# Accelerometer.net
KiCad netlist of a schematic drawn in Altium Designer
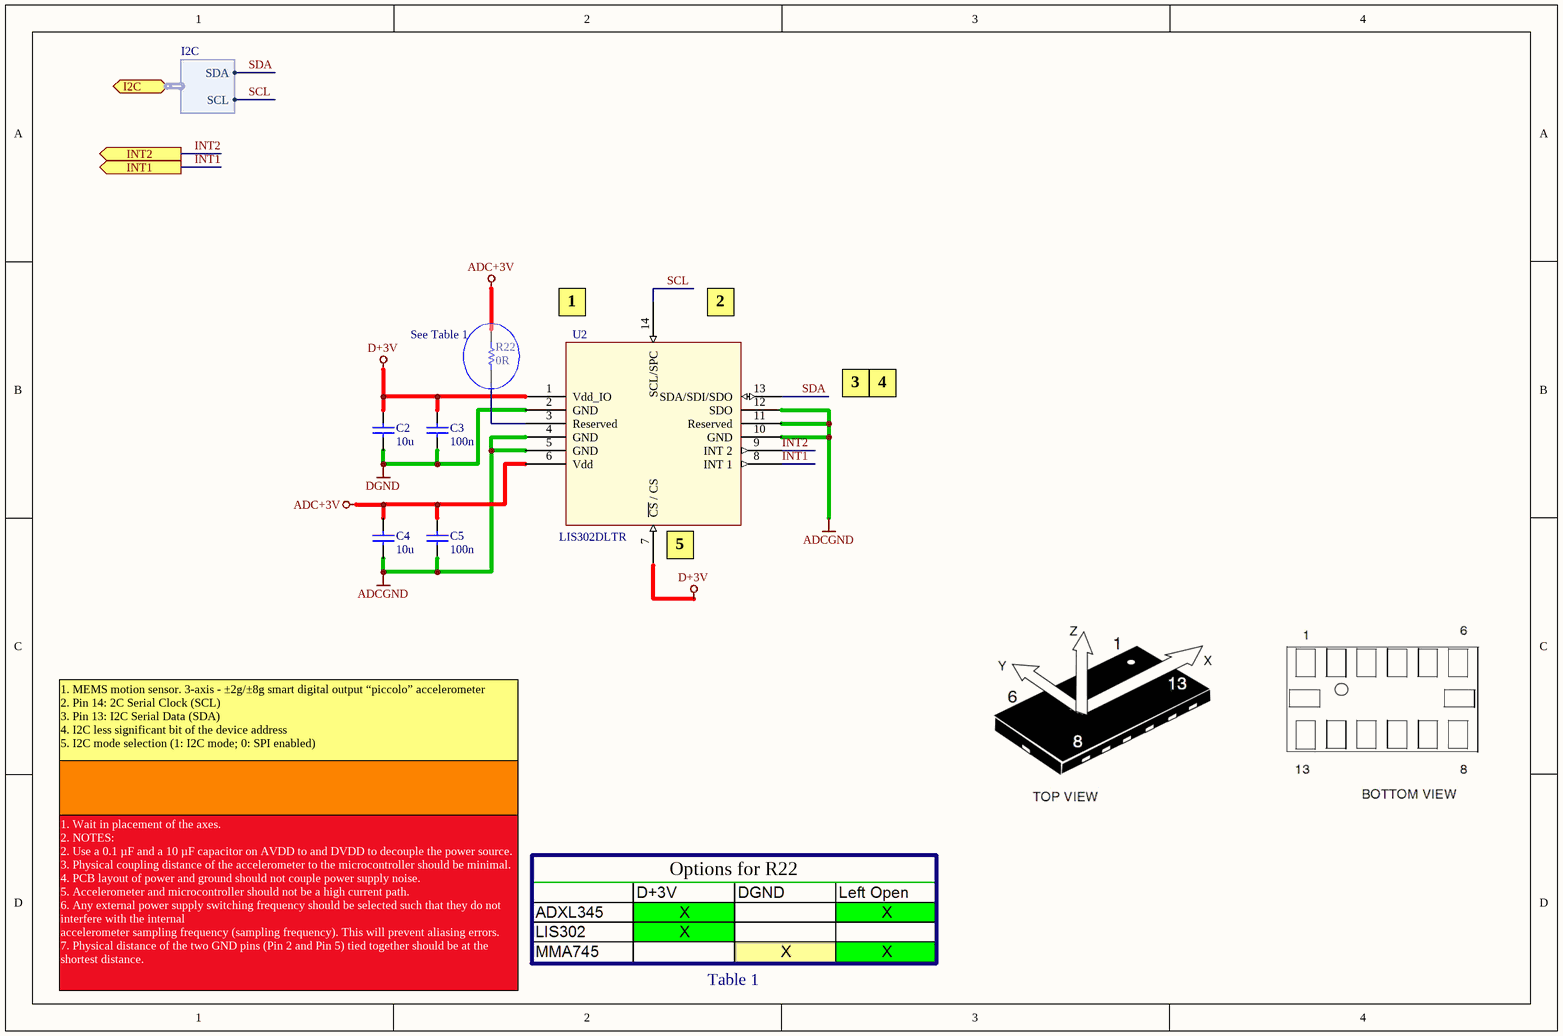
[diagram p0: Accelerometer.SchDoc]

(export (version "E")
  (design (tool "Eeschema 10.0.6"))
  (components
    (comp (ref "C2")
      (value "10u")
      (footprint "CC1608-0603")
      (description "CAP CER 10UF 6.3V X5R 0603")
      (fields (field (name "Comment") "Cap Semi"))
      (libsource (lib "Z1_Project") (part "Cap Semi"))
    )
    (comp (ref "C3")
      (value "100n")
      (footprint "CC-0402-AL")
      (description "Capacitor (Semiconductor SIM Model)")
      (fields (field (name "Comment") "Cap Semi"))
      (libsource (lib "Z1_Project") (part "Cap Semi"))
    )
    (comp (ref "C4")
      (value "10u")
      (footprint "CC1608-0603")
      (description "CAP CER 10UF 6.3V X5R 0603")
      (fields (field (name "Comment") "Cap Semi"))
      (libsource (lib "Z1_Project") (part "Cap Semi"))
    )
    (comp (ref "C5")
      (value "100n")
      (footprint "CC-0402-AL")
      (description "Capacitor (Semiconductor SIM Model)")
      (fields (field (name "Comment") "Cap Semi"))
      (libsource (lib "Z1_Project") (part "Cap Semi"))
    )
    (comp (ref "R22")
      (value "0R")
      (footprint "CR-0402-AL")
      (description "Semiconductor Resistor")
      (fields (field (name "MANUFACTURER") "Generic Components") (field (name "Comment") "Res Semi"))
      (libsource (lib "Z1_Project") (part "Res Semi"))
    )
    (comp (ref "U2")
      (value "LIS302DLTR")
      (footprint "LGA-3x5x1 0.8 - 1.5")
      (description "MEMS motion sensor  3-axis - ±2g/±8g smart digital output “piccolo” accelerometer")
      (libsource (lib "Z1_Project") (part "LIS302DL"))
    )
  )
  (nets
    (net (code "2") (name "/INT1") (class "Default")
      (node (ref "U2") (pin "8") (pinfunction "INT_1_8") (pintype "output"))
    )
    (net (code "3") (name "/INT2") (class "Default")
      (node (ref "U2") (pin "9") (pinfunction "INT_2_9") (pintype "output"))
    )
    (net (code "4") (name "/SCL") (class "Default")
      (node (ref "U2") (pin "14") (pinfunction "SCL/SPC_14") (pintype "input"))
    )
    (net (code "5") (name "/SDA") (class "Default")
      (node (ref "U2") (pin "13") (pinfunction "SDA/SDI/SDO_13") (pintype "bidirectional"))
    )
    (net (code "7") (name "ADC+3V") (class "Default")
      (node (ref "C4") (pin "2") (pinfunction "2_2") (pintype "passive"))
      (node (ref "C5") (pin "2") (pinfunction "2_2") (pintype "passive"))
      (node (ref "R22") (pin "2") (pinfunction "2_2") (pintype "passive"))
      (node (ref "U2") (pin "6") (pinfunction "Vdd_6") (pintype "power_in"))
    )
    (net (code "8") (name "ADCGND") (class "Default")
      (node (ref "C4") (pin "1") (pinfunction "1_1") (pintype "passive"))
      (node (ref "C5") (pin "1") (pinfunction "1_1") (pintype "passive"))
      (node (ref "U2") (pin "10") (pinfunction "GND_10") (pintype "power_in"))
      (node (ref "U2") (pin "11") (pinfunction "Reserved_11") (pintype "passive"))
      (node (ref "U2") (pin "12") (pinfunction "SDO_12") (pintype "passive"))
      (node (ref "U2") (pin "4") (pinfunction "GND_4") (pintype "power_in"))
      (node (ref "U2") (pin "5") (pinfunction "GND_5") (pintype "power_in"))
    )
    (net (code "9") (name "D+3V") (class "Default")
      (node (ref "C2") (pin "2") (pinfunction "2_2") (pintype "passive"))
      (node (ref "C3") (pin "2") (pinfunction "2_2") (pintype "passive"))
      (node (ref "U2") (pin "1") (pinfunction "Vdd_IO_1") (pintype "power_in"))
      (node (ref "U2") (pin "7") (pinfunction "~{CS}_/_CS_7") (pintype "input"))
    )
    (net (code "10") (name "DGND") (class "Default")
      (node (ref "C2") (pin "1") (pinfunction "1_1") (pintype "passive"))
      (node (ref "C3") (pin "1") (pinfunction "1_1") (pintype "passive"))
      (node (ref "U2") (pin "2") (pinfunction "GND_2") (pintype "power_in"))
    )
    (net (code "11") (name "Net-(R22-Pad1)") (class "Default")
      (node (ref "R22") (pin "1") (pinfunction "1_1") (pintype "passive"))
      (node (ref "U2") (pin "3") (pinfunction "Reserved_3") (pintype "passive"))
    )
  )
)
